# as14120_x31_usb.net
KiCad netlist of a schematic drawn in Altium Designer
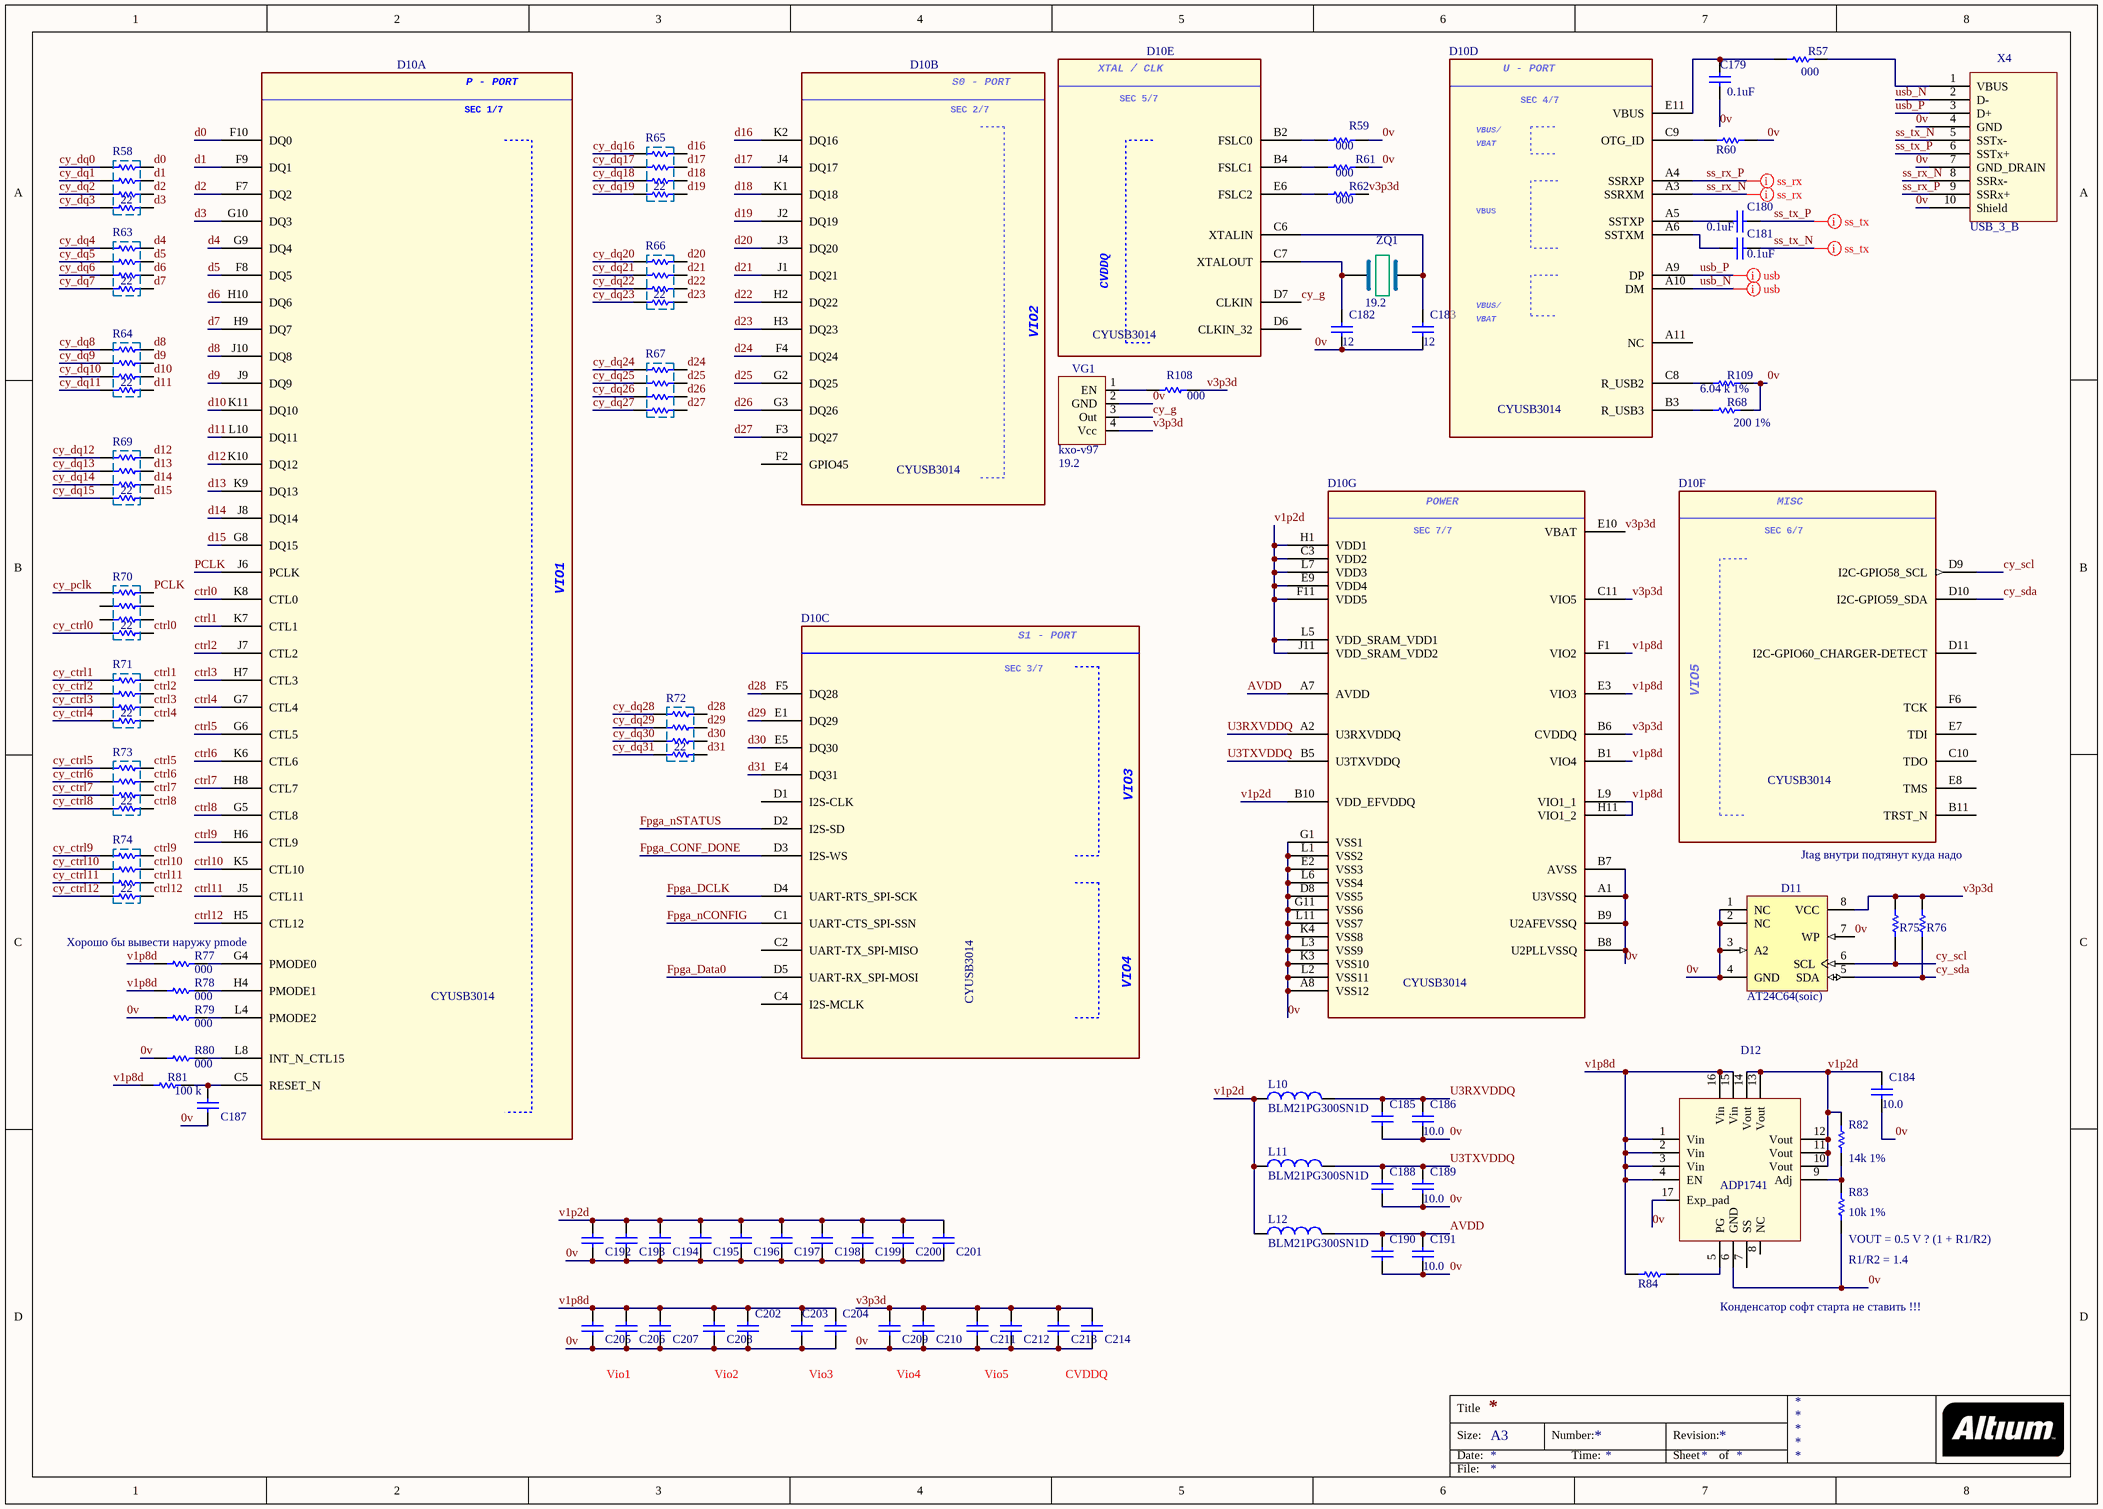
[diagram p0: as14120_x31_usb.SchDoc]

(export (version "E")
  (design (tool "Eeschema 10.0.6"))
  (components
    (comp (ref "C179")
      (value "0.1uF")
      (footprint "CAPC0402(1005)60_M")
      (description "CAP 1uF 10V ±20% 0402 (1005 Metric) Thickness 0.6mm SMD")
      (fields (field (name "TOLERANCE") "±20%") (field (name "Comment") "CAP 1uF 10V 0402(1005)"))
      (libsource (lib "as14120") (part "CAP_0402"))
    )
    (comp (ref "C180")
      (value "0.1uF")
      (footprint "CAPC0402(1005)60_M")
      (description "CAP 1uF 10V ±20% 0402 (1005 Metric) Thickness 0.6mm SMD")
      (fields (field (name "TOLERANCE") "±20%") (field (name "Comment") "CAP 1uF 10V 0402(1005)"))
      (libsource (lib "as14120") (part "CAP_0402"))
    )
    (comp (ref "C181")
      (value "0.1uF")
      (footprint "CAPC0402(1005)60_M")
      (description "CAP 1uF 10V ±20% 0402 (1005 Metric) Thickness 0.6mm SMD")
      (fields (field (name "TOLERANCE") "±20%") (field (name "Comment") "CAP 1uF 10V 0402(1005)"))
      (libsource (lib "as14120") (part "CAP_0402"))
    )
    (comp (ref "C182")
      (value "12")
      (footprint "CAPC0805(2012)100_N")
      (fields (field (name "Comment") "CAP_0805"))
      (libsource (lib "as14120") (part "CAP_0805"))
    )
    (comp (ref "C183")
      (value "12")
      (footprint "CAPC0805(2012)100_N")
      (fields (field (name "Comment") "CAP_0805"))
      (libsource (lib "as14120") (part "CAP_0805"))
    )
    (comp (ref "C184")
      (value "10.0")
      (footprint "CAPC0805(2012)100_N")
      (fields (field (name "Comment") "CAP_0805"))
      (libsource (lib "as14120") (part "CAP_0805"))
    )
    (comp (ref "C185")
      (value "CAP 1uF 10V 0402(1005)")
      (footprint "CAPC0402(1005)60_M")
      (description "CAP 1uF 10V ±20% 0402 (1005 Metric) Thickness 0.6mm SMD")
      (fields (field (name "TOLERANCE") "±20%"))
      (libsource (lib "as14120") (part "CAP_0402"))
    )
    (comp (ref "C186")
      (value "10.0")
      (footprint "CAPC0805(2012)100_N")
      (fields (field (name "Comment") "CAP_0805"))
      (libsource (lib "as14120") (part "CAP_0805"))
    )
    (comp (ref "C187")
      (value "CAP 1uF 10V 0402(1005)")
      (footprint "CAPC0402(1005)60_M")
      (description "CAP 1uF 10V ±20% 0402 (1005 Metric) Thickness 0.6mm SMD")
      (fields (field (name "TOLERANCE") "±20%"))
      (libsource (lib "as14120") (part "CAP_0402"))
    )
    (comp (ref "C188")
      (value "CAP 1uF 10V 0402(1005)")
      (footprint "CAPC0402(1005)60_M")
      (description "CAP 1uF 10V ±20% 0402 (1005 Metric) Thickness 0.6mm SMD")
      (fields (field (name "TOLERANCE") "±20%"))
      (libsource (lib "as14120") (part "CAP_0402"))
    )
    (comp (ref "C189")
      (value "10.0")
      (footprint "CAPC0805(2012)100_N")
      (fields (field (name "Comment") "CAP_0805"))
      (libsource (lib "as14120") (part "CAP_0805"))
    )
    (comp (ref "C190")
      (value "CAP 1uF 10V 0402(1005)")
      (footprint "CAPC0402(1005)60_M")
      (description "CAP 1uF 10V ±20% 0402 (1005 Metric) Thickness 0.6mm SMD")
      (fields (field (name "TOLERANCE") "±20%"))
      (libsource (lib "as14120") (part "CAP_0402"))
    )
    (comp (ref "C191")
      (value "10.0")
      (footprint "CAPC0805(2012)100_N")
      (fields (field (name "Comment") "CAP_0805"))
      (libsource (lib "as14120") (part "CAP_0805"))
    )
    (comp (ref "C192")
      (value "CAP 1uF 10V 0402(1005)")
      (footprint "CAPC0402(1005)60_M")
      (description "CAP 1uF 10V ±20% 0402 (1005 Metric) Thickness 0.6mm SMD")
      (fields (field (name "TOLERANCE") "±20%"))
      (libsource (lib "as14120") (part "CAP_0402"))
    )
    (comp (ref "C193")
      (value "CAP 1uF 10V 0402(1005)")
      (footprint "CAPC0402(1005)60_M")
      (description "CAP 1uF 10V ±20% 0402 (1005 Metric) Thickness 0.6mm SMD")
      (fields (field (name "TOLERANCE") "±20%"))
      (libsource (lib "as14120") (part "CAP_0402"))
    )
    (comp (ref "C194")
      (value "CAP 1uF 10V 0402(1005)")
      (footprint "CAPC0402(1005)60_M")
      (description "CAP 1uF 10V ±20% 0402 (1005 Metric) Thickness 0.6mm SMD")
      (fields (field (name "TOLERANCE") "±20%"))
      (libsource (lib "as14120") (part "CAP_0402"))
    )
    (comp (ref "C195")
      (value "CAP 1uF 10V 0402(1005)")
      (footprint "CAPC0402(1005)60_M")
      (description "CAP 1uF 10V ±20% 0402 (1005 Metric) Thickness 0.6mm SMD")
      (fields (field (name "TOLERANCE") "±20%"))
      (libsource (lib "as14120") (part "CAP_0402"))
    )
    (comp (ref "C196")
      (value "CAP 1uF 10V 0402(1005)")
      (footprint "CAPC0402(1005)60_M")
      (description "CAP 1uF 10V ±20% 0402 (1005 Metric) Thickness 0.6mm SMD")
      (fields (field (name "TOLERANCE") "±20%"))
      (libsource (lib "as14120") (part "CAP_0402"))
    )
    (comp (ref "C197")
      (value "CAP 1uF 10V 0402(1005)")
      (footprint "CAPC0402(1005)60_M")
      (description "CAP 1uF 10V ±20% 0402 (1005 Metric) Thickness 0.6mm SMD")
      (fields (field (name "TOLERANCE") "±20%"))
      (libsource (lib "as14120") (part "CAP_0402"))
    )
    (comp (ref "C198")
      (value "CAP 1uF 10V 0402(1005)")
      (footprint "CAPC0402(1005)60_M")
      (description "CAP 1uF 10V ±20% 0402 (1005 Metric) Thickness 0.6mm SMD")
      (fields (field (name "TOLERANCE") "±20%"))
      (libsource (lib "as14120") (part "CAP_0402"))
    )
    (comp (ref "C199")
      (value "CAP 1uF 10V 0402(1005)")
      (footprint "CAPC0402(1005)60_M")
      (description "CAP 1uF 10V ±20% 0402 (1005 Metric) Thickness 0.6mm SMD")
      (fields (field (name "TOLERANCE") "±20%"))
      (libsource (lib "as14120") (part "CAP_0402"))
    )
    (comp (ref "C200")
      (value "CAP 1uF 10V 0402(1005)")
      (footprint "CAPC0402(1005)60_M")
      (description "CAP 1uF 10V ±20% 0402 (1005 Metric) Thickness 0.6mm SMD")
      (fields (field (name "TOLERANCE") "±20%"))
      (libsource (lib "as14120") (part "CAP_0402"))
    )
    (comp (ref "C201")
      (value "CAP 1uF 10V 0402(1005)")
      (footprint "CAPC0402(1005)60_M")
      (description "CAP 1uF 10V ±20% 0402 (1005 Metric) Thickness 0.6mm SMD")
      (fields (field (name "TOLERANCE") "±20%"))
      (libsource (lib "as14120") (part "CAP_0402"))
    )
    (comp (ref "C202")
      (value "CAP 1uF 10V 0402(1005)")
      (footprint "CAPC0402(1005)60_M")
      (description "CAP 1uF 10V ±20% 0402 (1005 Metric) Thickness 0.6mm SMD")
      (fields (field (name "TOLERANCE") "±20%"))
      (libsource (lib "as14120") (part "CAP_0402"))
    )
    (comp (ref "C203")
      (value "CAP 1uF 10V 0402(1005)")
      (footprint "CAPC0402(1005)60_M")
      (description "CAP 1uF 10V ±20% 0402 (1005 Metric) Thickness 0.6mm SMD")
      (fields (field (name "TOLERANCE") "±20%"))
      (libsource (lib "as14120") (part "CAP_0402"))
    )
    (comp (ref "C204")
      (value "CAP 1uF 10V 0402(1005)")
      (footprint "CAPC0402(1005)60_M")
      (description "CAP 1uF 10V ±20% 0402 (1005 Metric) Thickness 0.6mm SMD")
      (fields (field (name "TOLERANCE") "±20%"))
      (libsource (lib "as14120") (part "CAP_0402"))
    )
    (comp (ref "C205")
      (value "CAP 1uF 10V 0402(1005)")
      (footprint "CAPC0402(1005)60_M")
      (description "CAP 1uF 10V ±20% 0402 (1005 Metric) Thickness 0.6mm SMD")
      (fields (field (name "TOLERANCE") "±20%"))
      (libsource (lib "as14120") (part "CAP_0402"))
    )
    (comp (ref "C206")
      (value "CAP 1uF 10V 0402(1005)")
      (footprint "CAPC0402(1005)60_M")
      (description "CAP 1uF 10V ±20% 0402 (1005 Metric) Thickness 0.6mm SMD")
      (fields (field (name "TOLERANCE") "±20%"))
      (libsource (lib "as14120") (part "CAP_0402"))
    )
    (comp (ref "C207")
      (value "CAP 1uF 10V 0402(1005)")
      (footprint "CAPC0402(1005)60_M")
      (description "CAP 1uF 10V ±20% 0402 (1005 Metric) Thickness 0.6mm SMD")
      (fields (field (name "TOLERANCE") "±20%"))
      (libsource (lib "as14120") (part "CAP_0402"))
    )
    (comp (ref "C208")
      (value "CAP 1uF 10V 0402(1005)")
      (footprint "CAPC0402(1005)60_M")
      (description "CAP 1uF 10V ±20% 0402 (1005 Metric) Thickness 0.6mm SMD")
      (fields (field (name "TOLERANCE") "±20%"))
      (libsource (lib "as14120") (part "CAP_0402"))
    )
    (comp (ref "C209")
      (value "CAP 1uF 10V 0402(1005)")
      (footprint "CAPC0402(1005)60_M")
      (description "CAP 1uF 10V ±20% 0402 (1005 Metric) Thickness 0.6mm SMD")
      (fields (field (name "TOLERANCE") "±20%"))
      (libsource (lib "as14120") (part "CAP_0402"))
    )
    (comp (ref "C210")
      (value "CAP 1uF 10V 0402(1005)")
      (footprint "CAPC0402(1005)60_M")
      (description "CAP 1uF 10V ±20% 0402 (1005 Metric) Thickness 0.6mm SMD")
      (fields (field (name "TOLERANCE") "±20%"))
      (libsource (lib "as14120") (part "CAP_0402"))
    )
    (comp (ref "C211")
      (value "CAP 1uF 10V 0402(1005)")
      (footprint "CAPC0402(1005)60_M")
      (description "CAP 1uF 10V ±20% 0402 (1005 Metric) Thickness 0.6mm SMD")
      (fields (field (name "TOLERANCE") "±20%"))
      (libsource (lib "as14120") (part "CAP_0402"))
    )
    (comp (ref "C212")
      (value "CAP 1uF 10V 0402(1005)")
      (footprint "CAPC0402(1005)60_M")
      (description "CAP 1uF 10V ±20% 0402 (1005 Metric) Thickness 0.6mm SMD")
      (fields (field (name "TOLERANCE") "±20%"))
      (libsource (lib "as14120") (part "CAP_0402"))
    )
    (comp (ref "C213")
      (value "CAP 1uF 10V 0402(1005)")
      (footprint "CAPC0402(1005)60_M")
      (description "CAP 1uF 10V ±20% 0402 (1005 Metric) Thickness 0.6mm SMD")
      (fields (field (name "TOLERANCE") "±20%"))
      (libsource (lib "as14120") (part "CAP_0402"))
    )
    (comp (ref "C214")
      (value "CAP 1uF 10V 0402(1005)")
      (footprint "CAPC0402(1005)60_M")
      (description "CAP 1uF 10V ±20% 0402 (1005 Metric) Thickness 0.6mm SMD")
      (fields (field (name "TOLERANCE") "±20%"))
      (libsource (lib "as14120") (part "CAP_0402"))
    )
    (comp (ref "D10")
      (value "CYUSB3014")
      (footprint "BGA121C80P11X11")
      (libsource (lib "") (part "CYUSB3014-BZXC_1"))
    )
    (comp (ref "D11")
      (value "AT24C64(soic)")
      (footprint "8S1_N")
      (libsource (lib "Atmel Serial EEPROM") (part "AT24C08BN-SP25-T"))
    )
    (comp (ref "D12") (value "ADP1741") (footprint "CP-16-4_N") (libsource (lib "as14120") (part "ADP1741")))
    (comp (ref "L10")
      (value "BLM21PG300SN1D")
      (footprint "CAPC0805(2012)100_N")
      (libsource (lib "as14120") (part "Ferrite_beat"))
    )
    (comp (ref "L11")
      (value "BLM21PG300SN1D")
      (footprint "CAPC0805(2012)100_N")
      (libsource (lib "as14120") (part "Ferrite_beat"))
    )
    (comp (ref "L12")
      (value "BLM21PG300SN1D")
      (footprint "CAPC0805(2012)100_N")
      (libsource (lib "as14120") (part "Ferrite_beat"))
    )
    (comp (ref "R57")
      (value "000")
      (footprint "RESC0805(2012)_L")
      (description "1K 0.125W 1% 0805 (2012 Metric)  SMD")
      (fields (field (name "TOLERANCE") "1 %") (field (name "POWER") "0.125 W"))
      (libsource (lib "as14120") (part "RES_0805"))
    )
    (comp (ref "R58") (value "22") (footprint "CAY16") (libsource (lib "as14120") (part "cay16-J4")))
    (comp (ref "R59")
      (value "000")
      (footprint "RESC0603(1608)_L")
      (description "1K 0.1W 5% 0603 (1608 Metric)  SMD")
      (fields (field (name "TOLERANCE") "5 %") (field (name "POWER") "0.1 W"))
      (libsource (lib "as14120") (part "RES_0603"))
    )
    (comp (ref "R60")
      (value "???")
      (footprint "RESC0603(1608)_L")
      (description "1K 0.1W 5% 0603 (1608 Metric)  SMD")
      (fields (field (name "TOLERANCE") "5 %") (field (name "POWER") "0.1 W"))
      (libsource (lib "as14120") (part "RES_0603"))
    )
    (comp (ref "R61")
      (value "000")
      (footprint "RESC0603(1608)_L")
      (description "1K 0.1W 5% 0603 (1608 Metric)  SMD")
      (fields (field (name "TOLERANCE") "5 %") (field (name "POWER") "0.1 W"))
      (libsource (lib "as14120") (part "RES_0603"))
    )
    (comp (ref "R62")
      (value "000")
      (footprint "RESC0603(1608)_L")
      (description "1K 0.1W 5% 0603 (1608 Metric)  SMD")
      (fields (field (name "TOLERANCE") "5 %") (field (name "POWER") "0.1 W"))
      (libsource (lib "as14120") (part "RES_0603"))
    )
    (comp (ref "R63") (value "22") (footprint "CAY16") (libsource (lib "as14120") (part "cay16-J4")))
    (comp (ref "R64") (value "22") (footprint "CAY16") (libsource (lib "as14120") (part "cay16-J4")))
    (comp (ref "R65") (value "22") (footprint "CAY16") (libsource (lib "as14120") (part "cay16-J4")))
    (comp (ref "R66") (value "22") (footprint "CAY16") (libsource (lib "as14120") (part "cay16-J4")))
    (comp (ref "R67") (value "~") (footprint "CAY16") (libsource (lib "as14120") (part "cay16-J4")))
    (comp (ref "R68")
      (value "200 1%")
      (footprint "RESC0805(2012)_L")
      (description "1K 0.125W 1% 0805 (2012 Metric)  SMD")
      (fields (field (name "TOLERANCE") "1 %") (field (name "POWER") "0.125 W"))
      (libsource (lib "as14120") (part "RES_0805"))
    )
    (comp (ref "R69") (value "22") (footprint "CAY16") (libsource (lib "as14120") (part "cay16-J4")))
    (comp (ref "R70") (value "22") (footprint "CAY16") (libsource (lib "as14120") (part "cay16-J4")))
    (comp (ref "R71") (value "22") (footprint "CAY16") (libsource (lib "as14120") (part "cay16-J4")))
    (comp (ref "R72") (value "22") (footprint "CAY16") (libsource (lib "as14120") (part "cay16-J4")))
    (comp (ref "R73") (value "22") (footprint "CAY16") (libsource (lib "as14120") (part "cay16-J4")))
    (comp (ref "R74") (value "22") (footprint "CAY16") (libsource (lib "as14120") (part "cay16-J4")))
    (comp (ref "R75")
      (value "1K 5% 0603(1608)")
      (footprint "RESC0603(1608)_L")
      (description "1K 0.1W 5% 0603 (1608 Metric)  SMD")
      (fields (field (name "TOLERANCE") "5 %") (field (name "POWER") "0.1 W"))
      (libsource (lib "as14120") (part "RES_0603"))
    )
    (comp (ref "R76")
      (value "1K 5% 0603(1608)")
      (footprint "RESC0603(1608)_L")
      (description "1K 0.1W 5% 0603 (1608 Metric)  SMD")
      (fields (field (name "TOLERANCE") "5 %") (field (name "POWER") "0.1 W"))
      (libsource (lib "as14120") (part "RES_0603"))
    )
    (comp (ref "R77")
      (value "000")
      (footprint "RESC0603(1608)_L")
      (description "1K 0.1W 5% 0603 (1608 Metric)  SMD")
      (fields (field (name "TOLERANCE") "5 %") (field (name "POWER") "0.1 W"))
      (libsource (lib "as14120") (part "RES_0603"))
    )
    (comp (ref "R78")
      (value "000")
      (footprint "RESC0603(1608)_L")
      (description "1K 0.1W 5% 0603 (1608 Metric)  SMD")
      (fields (field (name "TOLERANCE") "5 %") (field (name "POWER") "0.1 W"))
      (libsource (lib "as14120") (part "RES_0603"))
    )
    (comp (ref "R79")
      (value "000")
      (footprint "RESC0603(1608)_L")
      (description "1K 0.1W 5% 0603 (1608 Metric)  SMD")
      (fields (field (name "TOLERANCE") "5 %") (field (name "POWER") "0.1 W"))
      (libsource (lib "as14120") (part "RES_0603"))
    )
    (comp (ref "R80")
      (value "000")
      (footprint "RESC0603(1608)_L")
      (description "1K 0.1W 5% 0603 (1608 Metric)  SMD")
      (fields (field (name "TOLERANCE") "5 %") (field (name "POWER") "0.1 W"))
      (libsource (lib "as14120") (part "RES_0603"))
    )
    (comp (ref "R81")
      (value "100 k")
      (footprint "RESC0603(1608)_L")
      (description "1K 0.1W 5% 0603 (1608 Metric)  SMD")
      (fields (field (name "TOLERANCE") "5 %") (field (name "POWER") "0.1 W"))
      (libsource (lib "as14120") (part "RES_0603"))
    )
    (comp (ref "R82")
      (value "14k 1%")
      (footprint "RESC0805(2012)_L")
      (description "1K 0.125W 1% 0805 (2012 Metric)  SMD")
      (fields (field (name "TOLERANCE") "1 %") (field (name "POWER") "0.125 W"))
      (libsource (lib "as14120") (part "RES_0805"))
    )
    (comp (ref "R83")
      (value "10k 1%")
      (footprint "RESC0805(2012)_L")
      (description "1K 0.125W 1% 0805 (2012 Metric)  SMD")
      (fields (field (name "TOLERANCE") "1 %") (field (name "POWER") "0.125 W"))
      (libsource (lib "as14120") (part "RES_0805"))
    )
    (comp (ref "R84")
      (value "1K 5% 0603(1608)")
      (footprint "RESC0603(1608)_L")
      (description "1K 0.1W 5% 0603 (1608 Metric)  SMD")
      (fields (field (name "TOLERANCE") "5 %") (field (name "POWER") "0.1 W"))
      (libsource (lib "as14120") (part "RES_0603"))
    )
    (comp (ref "R108")
      (value "000")
      (footprint "RESC0603(1608)_L")
      (description "1K 0.1W 5% 0603 (1608 Metric)  SMD")
      (fields (field (name "TOLERANCE") "5 %") (field (name "POWER") "0.1 W"))
      (libsource (lib "as14120") (part "RES_0603"))
    )
    (comp (ref "R109")
      (value "6.04 k 1%")
      (footprint "RESC0805(2012)_L")
      (description "1K 0.125W 1% 0805 (2012 Metric)  SMD")
      (fields (field (name "TOLERANCE") "1 %") (field (name "POWER") "0.125 W"))
      (libsource (lib "as14120") (part "RES_0805"))
    )
    (comp (ref "VG1")
      (value "kxo-v97")
      (footprint "kxo-v97")
      (fields (field (name "ALTIUM_VALUE") "19.2"))
      (libsource (lib "as14120") (part "kxo-v97"))
    )
    (comp (ref "X4") (value "USB_3_B") (footprint "USB3_B") (libsource (lib "as14120") (part "USB_3_B")))
    (comp (ref "ZQ1")
      (value "19.2")
      (footprint "BCY-W2/E4.7")
      (fields (field (name "Comment") "Resonator"))
      (libsource (lib "as14120") (part "Resonator"))
    )
  )
  (nets
    (net (code "1") (name "/0v") (class "Default")
      (node (ref "C179") (pin "2") (pinfunction "2_2") (pintype "passive"))
      (node (ref "C182") (pin "1") (pinfunction "1_1") (pintype "passive"))
      (node (ref "C183") (pin "1") (pinfunction "1_1") (pintype "passive"))
      (node (ref "C184") (pin "1") (pinfunction "1_1") (pintype "passive"))
      (node (ref "C185") (pin "1") (pinfunction "1_1") (pintype "passive"))
      (node (ref "C186") (pin "1") (pinfunction "1_1") (pintype "passive"))
      (node (ref "C187") (pin "1") (pinfunction "1_1") (pintype "passive"))
      (node (ref "C188") (pin "1") (pinfunction "1_1") (pintype "passive"))
      (node (ref "C189") (pin "1") (pinfunction "1_1") (pintype "passive"))
      (node (ref "C190") (pin "1") (pinfunction "1_1") (pintype "passive"))
      (node (ref "C191") (pin "1") (pinfunction "1_1") (pintype "passive"))
      (node (ref "C192") (pin "1") (pinfunction "1_1") (pintype "passive"))
      (node (ref "C193") (pin "1") (pinfunction "1_1") (pintype "passive"))
      (node (ref "C194") (pin "1") (pinfunction "1_1") (pintype "passive"))
      (node (ref "C195") (pin "1") (pinfunction "1_1") (pintype "passive"))
      (node (ref "C196") (pin "1") (pinfunction "1_1") (pintype "passive"))
      (node (ref "C197") (pin "1") (pinfunction "1_1") (pintype "passive"))
      (node (ref "C198") (pin "1") (pinfunction "1_1") (pintype "passive"))
      (node (ref "C199") (pin "1") (pinfunction "1_1") (pintype "passive"))
      (node (ref "C200") (pin "1") (pinfunction "1_1") (pintype "passive"))
      (node (ref "C201") (pin "1") (pinfunction "1_1") (pintype "passive"))
      (node (ref "C202") (pin "1") (pinfunction "1_1") (pintype "passive"))
      (node (ref "C203") (pin "1") (pinfunction "1_1") (pintype "passive"))
      (node (ref "C204") (pin "1") (pinfunction "1_1") (pintype "passive"))
      (node (ref "C205") (pin "1") (pinfunction "1_1") (pintype "passive"))
      (node (ref "C206") (pin "1") (pinfunction "1_1") (pintype "passive"))
      (node (ref "C207") (pin "1") (pinfunction "1_1") (pintype "passive"))
      (node (ref "C208") (pin "1") (pinfunction "1_1") (pintype "passive"))
      (node (ref "C209") (pin "1") (pinfunction "1_1") (pintype "passive"))
      (node (ref "C210") (pin "1") (pinfunction "1_1") (pintype "passive"))
      (node (ref "C211") (pin "1") (pinfunction "1_1") (pintype "passive"))
      (node (ref "C212") (pin "1") (pinfunction "1_1") (pintype "passive"))
      (node (ref "C213") (pin "1") (pinfunction "1_1") (pintype "passive"))
      (node (ref "C214") (pin "1") (pinfunction "1_1") (pintype "passive"))
      (node (ref "D10") (pin "A1") (pinfunction "U3VSSQ_A1") (pintype "passive"))
      (node (ref "D10") (pin "A8") (pinfunction "VSS12_A8") (pintype "passive"))
      (node (ref "D10") (pin "B7") (pinfunction "AVSS_B7") (pintype "passive"))
      (node (ref "D10") (pin "B8") (pinfunction "U2PLLVSSQ_B8") (pintype "passive"))
      (node (ref "D10") (pin "B9") (pinfunction "U2AFEVSSQ_B9") (pintype "passive"))
      (node (ref "D10") (pin "D8") (pinfunction "VSS5_D8") (pintype "passive"))
      (node (ref "D10") (pin "E2") (pinfunction "VSS3_E2") (pintype "passive"))
      (node (ref "D10") (pin "G1") (pinfunction "VSS1_G1") (pintype "passive"))
      (node (ref "D10") (pin "G11") (pinfunction "VSS6_G11") (pintype "passive"))
      (node (ref "D10") (pin "K3") (pinfunction "VSS10_K3") (pintype "passive"))
      (node (ref "D10") (pin "K4") (pinfunction "VSS8_K4") (pintype "passive"))
      (node (ref "D10") (pin "L1") (pinfunction "VSS2_L1") (pintype "passive"))
      (node (ref "D10") (pin "L11") (pinfunction "VSS7_L11") (pintype "passive"))
      (node (ref "D10") (pin "L2") (pinfunction "VSS11_L2") (pintype "passive"))
      (node (ref "D10") (pin "L3") (pinfunction "VSS9_L3") (pintype "passive"))
      (node (ref "D10") (pin "L6") (pinfunction "VSS4_L6") (pintype "passive"))
      (node (ref "D11") (pin "1") (pinfunction "NC_1") (pintype "passive"))
      (node (ref "D11") (pin "2") (pinfunction "NC_2") (pintype "passive"))
      (node (ref "D11") (pin "3") (pinfunction "A2_3") (pintype "input"))
      (node (ref "D11") (pin "4") (pinfunction "GND_4") (pintype "power_in"))
      (node (ref "D11") (pin "7") (pinfunction "WP_7") (pintype "input"))
      (node (ref "D12") (pin "17") (pinfunction "Exp_pad_17") (pintype "passive"))
      (node (ref "D12") (pin "6") (pinfunction "GND_6") (pintype "passive"))
      (node (ref "R109") (pin "2") (pinfunction "2_2") (pintype "passive"))
      (node (ref "R59") (pin "1") (pinfunction "1_1") (pintype "passive"))
      (node (ref "R60") (pin "2") (pinfunction "2_2") (pintype "passive"))
      (node (ref "R61") (pin "1") (pinfunction "1_1") (pintype "passive"))
      (node (ref "R68") (pin "2") (pinfunction "2_2") (pintype "passive"))
      (node (ref "R79") (pin "2") (pinfunction "2_2") (pintype "passive"))
      (node (ref "R80") (pin "2") (pinfunction "2_2") (pintype "passive"))
      (node (ref "R83") (pin "1") (pinfunction "1_1") (pintype "passive"))
      (node (ref "VG1") (pin "2") (pinfunction "GND_2") (pintype "passive"))
      (node (ref "X4") (pin "10") (pinfunction "Shield_10") (pintype "passive"))
      (node (ref "X4") (pin "4") (pinfunction "GND_4") (pintype "passive"))
      (node (ref "X4") (pin "7") (pinfunction "GND_DRAIN_7") (pintype "passive"))
    )
    (net (code "2") (name "/AVDD") (class "Default")
      (node (ref "C190") (pin "2") (pinfunction "2_2") (pintype "passive"))
      (node (ref "C191") (pin "2") (pinfunction "2_2") (pintype "passive"))
      (node (ref "D10") (pin "A7") (pinfunction "AVDD_A7") (pintype "passive"))
      (node (ref "L12") (pin "2") (pinfunction "2_2") (pintype "passive"))
    )
    (net (code "3") (name "/Fpga_CONF_DONE") (class "Default")
      (node (ref "D10") (pin "D3") (pinfunction "I2S-WS_D3") (pintype "passive"))
    )
    (net (code "4") (name "/Fpga_DCLK") (class "Default")
      (node (ref "D10") (pin "D4") (pinfunction "UART-RTS_SPI-SCK_D4") (pintype "passive"))
    )
    (net (code "5") (name "/Fpga_Data0") (class "Default")
      (node (ref "D10") (pin "D5") (pinfunction "UART-RX_SPI-MOSI_D5") (pintype "passive"))
    )
    (net (code "6") (name "/Fpga_nCONFIG") (class "Default")
      (node (ref "D10") (pin "C1") (pinfunction "UART-CTS_SPI-SSN_C1") (pintype "passive"))
    )
    (net (code "7") (name "/Fpga_nSTATUS") (class "Default")
      (node (ref "D10") (pin "D2") (pinfunction "I2S-SD_D2") (pintype "passive"))
    )
    (net (code "8") (name "/PCLK") (class "Default")
      (node (ref "D10") (pin "J6") (pinfunction "PCLK_J6") (pintype "passive"))
      (node (ref "R70") (pin "8") (pinfunction "8_8") (pintype "passive"))
    )
    (net (code "9") (name "/U3RXVDDQ") (class "Default")
      (node (ref "C185") (pin "2") (pinfunction "2_2") (pintype "passive"))
      (node (ref "C186") (pin "2") (pinfunction "2_2") (pintype "passive"))
      (node (ref "D10") (pin "A2") (pinfunction "U3RXVDDQ_A2") (pintype "passive"))
      (node (ref "L10") (pin "2") (pinfunction "2_2") (pintype "passive"))
    )
    (net (code "10") (name "/U3TXVDDQ") (class "Default")
      (node (ref "C188") (pin "2") (pinfunction "2_2") (pintype "passive"))
      (node (ref "C189") (pin "2") (pinfunction "2_2") (pintype "passive"))
      (node (ref "D10") (pin "B5") (pinfunction "U3TXVDDQ_B5") (pintype "passive"))
      (node (ref "L11") (pin "2") (pinfunction "2_2") (pintype "passive"))
    )
    (net (code "11") (name "/ctrl0") (class "Default")
      (node (ref "D10") (pin "K8") (pinfunction "CTL0_K8") (pintype "passive"))
      (node (ref "R70") (pin "5") (pinfunction "5_5") (pintype "passive"))
    )
    (net (code "12") (name "/ctrl1") (class "Default")
      (node (ref "D10") (pin "K7") (pinfunction "CTL1_K7") (pintype "passive"))
      (node (ref "R71") (pin "8") (pinfunction "8_8") (pintype "passive"))
    )
    (net (code "13") (name "/ctrl2") (class "Default")
      (node (ref "D10") (pin "J7") (pinfunction "CTL2_J7") (pintype "passive"))
      (node (ref "R71") (pin "7") (pinfunction "7_7") (pintype "passive"))
    )
    (net (code "14") (name "/ctrl3") (class "Default")
      (node (ref "D10") (pin "H7") (pinfunction "CTL3_H7") (pintype "passive"))
      (node (ref "R71") (pin "6") (pinfunction "6_6") (pintype "passive"))
    )
    (net (code "15") (name "/ctrl4") (class "Default")
      (node (ref "D10") (pin "G7") (pinfunction "CTL4_G7") (pintype "passive"))
      (node (ref "R71") (pin "5") (pinfunction "5_5") (pintype "passive"))
    )
    (net (code "16") (name "/ctrl5") (class "Default")
      (node (ref "D10") (pin "G6") (pinfunction "CTL5_G6") (pintype "passive"))
      (node (ref "R73") (pin "8") (pinfunction "8_8") (pintype "passive"))
    )
    (net (code "17") (name "/ctrl6") (class "Default")
      (node (ref "D10") (pin "K6") (pinfunction "CTL6_K6") (pintype "passive"))
      (node (ref "R73") (pin "7") (pinfunction "7_7") (pintype "passive"))
    )
    (net (code "18") (name "/ctrl7") (class "Default")
      (node (ref "D10") (pin "H8") (pinfunction "CTL7_H8") (pintype "passive"))
      (node (ref "R73") (pin "6") (pinfunction "6_6") (pintype "passive"))
    )
    (net (code "19") (name "/ctrl8") (class "Default")
      (node (ref "D10") (pin "G5") (pinfunction "CTL8_G5") (pintype "passive"))
      (node (ref "R73") (pin "5") (pinfunction "5_5") (pintype "passive"))
    )
    (net (code "20") (name "/ctrl9") (class "Default")
      (node (ref "D10") (pin "H6") (pinfunction "CTL9_H6") (pintype "passive"))
      (node (ref "R74") (pin "8") (pinfunction "8_8") (pintype "passive"))
    )
    (net (code "21") (name "/ctrl10") (class "Default")
      (node (ref "D10") (pin "K5") (pinfunction "CTL10_K5") (pintype "passive"))
      (node (ref "R74") (pin "7") (pinfunction "7_7") (pintype "passive"))
    )
    (net (code "22") (name "/ctrl11") (class "Default")
      (node (ref "D10") (pin "J5") (pinfunction "CTL11_J5") (pintype "passive"))
      (node (ref "R74") (pin "6") (pinfunction "6_6") (pintype "passive"))
    )
    (net (code "23") (name "/ctrl12") (class "Default")
      (node (ref "D10") (pin "H5") (pinfunction "CTL12_H5") (pintype "passive"))
      (node (ref "R74") (pin "5") (pinfunction "5_5") (pintype "passive"))
    )
    (net (code "24") (name "/cy_ctrl0") (class "Default")
      (node (ref "R70") (pin "4") (pinfunction "4_4") (pintype "passive"))
    )
    (net (code "25") (name "/cy_ctrl1") (class "Default")
      (node (ref "R71") (pin "1") (pinfunction "1_1") (pintype "passive"))
    )
    (net (code "26") (name "/cy_ctrl2") (class "Default")
      (node (ref "R71") (pin "2") (pinfunction "2_2") (pintype "passive"))
    )
    (net (code "27") (name "/cy_ctrl3") (class "Default")
      (node (ref "R71") (pin "3") (pinfunction "3_3") (pintype "passive"))
    )
    (net (code "28") (name "/cy_ctrl4") (class "Default")
      (node (ref "R71") (pin "4") (pinfunction "4_4") (pintype "passive"))
    )
    (net (code "29") (name "/cy_ctrl5") (class "Default")
      (node (ref "R73") (pin "1") (pinfunction "1_1") (pintype "passive"))
    )
    (net (code "30") (name "/cy_ctrl6") (class "Default")
      (node (ref "R73") (pin "2") (pinfunction "2_2") (pintype "passive"))
    )
    (net (code "31") (name "/cy_ctrl7") (class "Default")
      (node (ref "R73") (pin "3") (pinfunction "3_3") (pintype "passive"))
    )
    (net (code "32") (name "/cy_ctrl8") (class "Default")
      (node (ref "R73") (pin "4") (pinfunction "4_4") (pintype "passive"))
    )
    (net (code "33") (name "/cy_ctrl9") (class "Default")
      (node (ref "R74") (pin "1") (pinfunction "1_1") (pintype "passive"))
    )
    (net (code "34") (name "/cy_ctrl10") (class "Default")
      (node (ref "R74") (pin "2") (pinfunction "2_2") (pintype "passive"))
    )
    (net (code "35") (name "/cy_ctrl11") (class "Default")
      (node (ref "R74") (pin "3") (pinfunction "3_3") (pintype "passive"))
    )
    (net (code "36") (name "/cy_ctrl12") (class "Default")
      (node (ref "R74") (pin "4") (pinfunction "4_4") (pintype "passive"))
    )
    (net (code "37") (name "/cy_dq0") (class "Default")
      (node (ref "R58") (pin "1") (pinfunction "1_1") (pintype "passive"))
    )
    (net (code "38") (name "/cy_dq1") (class "Default")
      (node (ref "R58") (pin "2") (pinfunction "2_2") (pintype "passive"))
    )
    (net (code "39") (name "/cy_dq2") (class "Default")
      (node (ref "R58") (pin "3") (pinfunction "3_3") (pintype "passive"))
    )
    (net (code "40") (name "/cy_dq3") (class "Default")
      (node (ref "R58") (pin "4") (pinfunction "4_4") (pintype "passive"))
    )
    (net (code "41") (name "/cy_dq4") (class "Default")
      (node (ref "R63") (pin "1") (pinfunction "1_1") (pintype "passive"))
    )
    (net (code "42") (name "/cy_dq5") (class "Default")
      (node (ref "R63") (pin "2") (pinfunction "2_2") (pintype "passive"))
    )
    (net (code "43") (name "/cy_dq6") (class "Default")
      (node (ref "R63") (pin "3") (pinfunction "3_3") (pintype "passive"))
    )
    (net (code "44") (name "/cy_dq7") (class "Default")
      (node (ref "R63") (pin "4") (pinfunction "4_4") (pintype "passive"))
    )
    (net (code "45") (name "/cy_dq8") (class "Default")
      (node (ref "R64") (pin "1") (pinfunction "1_1") (pintype "passive"))
    )
    (net (code "46") (name "/cy_dq9") (class "Default")
      (node (ref "R64") (pin "2") (pinfunction "2_2") (pintype "passive"))
    )
    (net (code "47") (name "/cy_dq10") (class "Default")
      (node (ref "R64") (pin "3") (pinfunction "3_3") (pintype "passive"))
    )
    (net (code "48") (name "/cy_dq11") (class "Default")
      (node (ref "R64") (pin "4") (pinfunction "4_4") (pintype "passive"))
    )
    (net (code "49") (name "/cy_dq12") (class "Default")
      (node (ref "R69") (pin "1") (pinfunction "1_1") (pintype "passive"))
    )
    (net (code "50") (name "/cy_dq13") (class "Default")
      (node (ref "R69") (pin "2") (pinfunction "2_2") (pintype "passive"))
    )
    (net (code "51") (name "/cy_dq14") (class "Default")
      (node (ref "R69") (pin "3") (pinfunction "3_3") (pintype "passive"))
    )
    (net (code "52") (name "/cy_dq15") (class "Default")
      (node (ref "R69") (pin "4") (pinfunction "4_4") (pintype "passive"))
    )
    (net (code "53") (name "/cy_dq16") (class "Default")
      (node (ref "R65") (pin "1") (pinfunction "1_1") (pintype "passive"))
    )
    (net (code "54") (name "/cy_dq17") (class "Default")
      (node (ref "R65") (pin "2") (pinfunction "2_2") (pintype "passive"))
    )
    (net (code "55") (name "/cy_dq18") (class "Default")
      (node (ref "R65") (pin "3") (pinfunction "3_3") (pintype "passive"))
    )
    (net (code "56") (name "/cy_dq19") (class "Default")
      (node (ref "R65") (pin "4") (pinfunction "4_4") (pintype "passive"))
    )
    (net (code "57") (name "/cy_dq20") (class "Default")
      (node (ref "R66") (pin "1") (pinfunction "1_1") (pintype "passive"))
    )
    (net (code "58") (name "/cy_dq21") (class "Default")
      (node (ref "R66") (pin "2") (pinfunction "2_2") (pintype "passive"))
    )
    (net (code "59") (name "/cy_dq22") (class "Default")
      (node (ref "R66") (pin "3") (pinfunction "3_3") (pintype "passive"))
    )
    (net (code "60") (name "/cy_dq23") (class "Default")
      (node (ref "R66") (pin "4") (pinfunction "4_4") (pintype "passive"))
    )
    (net (code "61") (name "/cy_dq24") (class "Default")
      (node (ref "R67") (pin "1") (pinfunction "1_1") (pintype "passive"))
    )
    (net (code "62") (name "/cy_dq25") (class "Default")
      (node (ref "R67") (pin "2") (pinfunction "2_2") (pintype "passive"))
    )
    (net (code "63") (name "/cy_dq26") (class "Default")
      (node (ref "R67") (pin "3") (pinfunction "3_3") (pintype "passive"))
    )
    (net (code "64") (name "/cy_dq27") (class "Default")
      (node (ref "R67") (pin "4") (pinfunction "4_4") (pintype "passive"))
    )
    (net (code "65") (name "/cy_dq28") (class "Default")
      (node (ref "R72") (pin "1") (pinfunction "1_1") (pintype "passive"))
    )
    (net (code "66") (name "/cy_dq29") (class "Default")
      (node (ref "R72") (pin "2") (pinfunction "2_2") (pintype "passive"))
    )
    (net (code "67") (name "/cy_dq30") (class "Default")
      (node (ref "R72") (pin "3") (pinfunction "3_3") (pintype "passive"))
    )
    (net (code "68") (name "/cy_dq31") (class "Default")
      (node (ref "R72") (pin "4") (pinfunction "4_4") (pintype "passive"))
    )
    (net (code "69") (name "/cy_g") (class "Default")
      (node (ref "D10") (pin "D7") (pinfunction "CLKIN_D7") (pintype "passive"))
      (node (ref "VG1") (pin "3") (pinfunction "Out_3") (pintype "passive"))
    )
    (net (code "70") (name "/cy_pclk") (class "Default")
      (node (ref "R70") (pin "1") (pinfunction "1_1") (pintype "passive"))
    )
    (net (code "71") (name "/cy_scl") (class "Default")
      (node (ref "D10") (pin "D9") (pinfunction "I2C-GPIO58_SCL_D9") (pintype "output"))
      (node (ref "D11") (pin "6") (pinfunction "SCL_6") (pintype "input"))
      (node (ref "R75") (pin "1") (pinfunction "1_1") (pintype "passive"))
    )
    (net (code "72") (name "/cy_sda") (class "Default")
      (node (ref "D10") (pin "D10") (pinfunction "I2C-GPIO59_SDA_D10") (pintype "passive"))
      (node (ref "D11") (pin "5") (pinfunction "SDA_5") (pintype "bidirectional"))
      (node (ref "R76") (pin "1") (pinfunction "1_1") (pintype "passive"))
    )
    (net (code "73") (name "/d0") (class "Default")
      (node (ref "D10") (pin "F10") (pinfunction "DQ0_F10") (pintype "passive"))
      (node (ref "R58") (pin "8") (pinfunction "8_8") (pintype "passive"))
    )
    (net (code "74") (name "/d1") (class "Default")
      (node (ref "D10") (pin "F9") (pinfunction "DQ1_F9") (pintype "passive"))
      (node (ref "R58") (pin "7") (pinfunction "7_7") (pintype "passive"))
    )
    (net (code "75") (name "/d2") (class "Default")
      (node (ref "D10") (pin "F7") (pinfunction "DQ2_F7") (pintype "passive"))
      (node (ref "R58") (pin "6") (pinfunction "6_6") (pintype "passive"))
    )
    (net (code "76") (name "/d3") (class "Default")
      (node (ref "D10") (pin "G10") (pinfunction "DQ3_G10") (pintype "passive"))
      (node (ref "R58") (pin "5") (pinfunction "5_5") (pintype "passive"))
    )
    (net (code "77") (name "/d4") (class "Default")
      (node (ref "D10") (pin "G9") (pinfunction "DQ4_G9") (pintype "passive"))
      (node (ref "R63") (pin "8") (pinfunction "8_8") (pintype "passive"))
    )
    (net (code "78") (name "/d5") (class "Default")
      (node (ref "D10") (pin "F8") (pinfunction "DQ5_F8") (pintype "passive"))
      (node (ref "R63") (pin "7") (pinfunction "7_7") (pintype "passive"))
    )
    (net (code "79") (name "/d6") (class "Default")
      (node (ref "D10") (pin "H10") (pinfunction "DQ6_H10") (pintype "passive"))
      (node (ref "R63") (pin "6") (pinfunction "6_6") (pintype "passive"))
    )
    (net (code "80") (name "/d7") (class "Default")
      (node (ref "D10") (pin "H9") (pinfunction "DQ7_H9") (pintype "passive"))
      (node (ref "R63") (pin "5") (pinfunction "5_5") (pintype "passive"))
    )
    (net (code "81") (name "/d8") (class "Default")
      (node (ref "D10") (pin "J10") (pinfunction "DQ8_J10") (pintype "passive"))
      (node (ref "R64") (pin "8") (pinfunction "8_8") (pintype "passive"))
    )
    (net (code "82") (name "/d9") (class "Default")
      (node (ref "D10") (pin "J9") (pinfunction "DQ9_J9") (pintype "passive"))
      (node (ref "R64") (pin "7") (pinfunction "7_7") (pintype "passive"))
    )
    (net (code "83") (name "/d10") (class "Default")
      (node (ref "D10") (pin "K11") (pinfunction "DQ10_K11") (pintype "passive"))
      (node (ref "R64") (pin "6") (pinfunction "6_6") (pintype "passive"))
    )
    (net (code "84") (name "/d11") (class "Default")
      (node (ref "D10") (pin "L10") (pinfunction "DQ11_L10") (pintype "passive"))
      (node (ref "R64") (pin "5") (pinfunction "5_5") (pintype "passive"))
    )
    (net (code "85") (name "/d12") (class "Default")
      (node (ref "D10") (pin "K10") (pinfunction "DQ12_K10") (pintype "passive"))
      (node (ref "R69") (pin "8") (pinfunction "8_8") (pintype "passive"))
    )
    (net (code "86") (name "/d13") (class "Default")
      (node (ref "D10") (pin "K9") (pinfunction "DQ13_K9") (pintype "passive"))
      (node (ref "R69") (pin "7") (pinfunction "7_7") (pintype "passive"))
    )
    (net (code "87") (name "/d14") (class "Default")
      (node (ref "D10") (pin "J8") (pinfunction "DQ14_J8") (pintype "passive"))
      (node (ref "R69") (pin "6") (pinfunction "6_6") (pintype "passive"))
    )
    (net (code "88") (name "/d15") (class "Default")
      (node (ref "D10") (pin "G8") (pinfunction "DQ15_G8") (pintype "passive"))
      (node (ref "R69") (pin "5") (pinfunction "5_5") (pintype "passive"))
    )
    (net (code "89") (name "/d16") (class "Default")
      (node (ref "D10") (pin "K2") (pinfunction "DQ16_K2") (pintype "passive"))
      (node (ref "R65") (pin "8") (pinfunction "8_8") (pintype "passive"))
    )
    (net (code "90") (name "/d17") (class "Default")
      (node (ref "D10") (pin "J4") (pinfunction "DQ17_J4") (pintype "passive"))
      (node (ref "R65") (pin "7") (pinfunction "7_7") (pintype "passive"))
    )
    (net (code "91") (name "/d18") (class "Default")
      (node (ref "D10") (pin "K1") (pinfunction "DQ18_K1") (pintype "passive"))
      (node (ref "R65") (pin "6") (pinfunction "6_6") (pintype "passive"))
    )
    (net (code "92") (name "/d19") (class "Default")
      (node (ref "D10") (pin "J2") (pinfunction "DQ19_J2") (pintype "passive"))
      (node (ref "R65") (pin "5") (pinfunction "5_5") (pintype "passive"))
    )
    (net (code "93") (name "/d20") (class "Default")
      (node (ref "D10") (pin "J3") (pinfunction "DQ20_J3") (pintype "passive"))
      (node (ref "R66") (pin "8") (pinfunction "8_8") (pintype "passive"))
    )
    (net (code "94") (name "/d21") (class "Default")
      (node (ref "D10") (pin "J1") (pinfunction "DQ21_J1") (pintype "passive"))
      (node (ref "R66") (pin "7") (pinfunction "7_7") (pintype "passive"))
    )
    (net (code "95") (name "/d22") (class "Default")
      (node (ref "D10") (pin "H2") (pinfunction "DQ22_H2") (pintype "passive"))
      (node (ref "R66") (pin "6") (pinfunction "6_6") (pintype "passive"))
    )
    (net (code "96") (name "/d23") (class "Default")
      (node (ref "D10") (pin "H3") (pinfunction "DQ23_H3") (pintype "passive"))
      (node (ref "R66") (pin "5") (pinfunction "5_5") (pintype "passive"))
    )
    (net (code "97") (name "/d24") (class "Default")
      (node (ref "D10") (pin "F4") (pinfunction "DQ24_F4") (pintype "passive"))
      (node (ref "R67") (pin "8") (pinfunction "8_8") (pintype "passive"))
    )
    (net (code "98") (name "/d25") (class "Default")
      (node (ref "D10") (pin "G2") (pinfunction "DQ25_G2") (pintype "passive"))
      (node (ref "R67") (pin "7") (pinfunction "7_7") (pintype "passive"))
    )
    (net (code "99") (name "/d26") (class "Default")
      (node (ref "D10") (pin "G3") (pinfunction "DQ26_G3") (pintype "passive"))
      (node (ref "R67") (pin "6") (pinfunction "6_6") (pintype "passive"))
    )
    (net (code "100") (name "/d27") (class "Default")
      (node (ref "D10") (pin "F3") (pinfunction "DQ27_F3") (pintype "passive"))
      (node (ref "R67") (pin "5") (pinfunction "5_5") (pintype "passive"))
    )
    (net (code "101") (name "/d28") (class "Default")
      (node (ref "D10") (pin "F5") (pinfunction "DQ28_F5") (pintype "passive"))
      (node (ref "R72") (pin "8") (pinfunction "8_8") (pintype "passive"))
    )
    (net (code "102") (name "/d29") (class "Default")
      (node (ref "D10") (pin "E1") (pinfunction "DQ29_E1") (pintype "passive"))
      (node (ref "R72") (pin "7") (pinfunction "7_7") (pintype "passive"))
    )
    (net (code "103") (name "/d30") (class "Default")
      (node (ref "D10") (pin "E5") (pinfunction "DQ30_E5") (pintype "passive"))
      (node (ref "R72") (pin "6") (pinfunction "6_6") (pintype "passive"))
    )
    (net (code "104") (name "/d31") (class "Default")
      (node (ref "D10") (pin "E4") (pinfunction "DQ31_E4") (pintype "passive"))
      (node (ref "R72") (pin "5") (pinfunction "5_5") (pintype "passive"))
    )
    (net (code "105") (name "/ss_rx_N") (class "Default")
      (node (ref "D10") (pin "A3") (pinfunction "SSRXM_A3") (pintype "passive"))
      (node (ref "X4") (pin "8") (pinfunction "SSRx-_8") (pintype "passive"))
    )
    (net (code "106") (name "/ss_rx_P") (class "Default")
      (node (ref "D10") (pin "A4") (pinfunction "SSRXP_A4") (pintype "passive"))
      (node (ref "X4") (pin "9") (pinfunction "SSRx+_9") (pintype "passive"))
    )
    (net (code "107") (name "/ss_tx_N") (class "Default")
      (node (ref "C181") (pin "1") (pinfunction "1_1") (pintype "passive"))
      (node (ref "X4") (pin "5") (pinfunction "SSTx-_5") (pintype "passive"))
    )
    (net (code "108") (name "/ss_tx_P") (class "Default")
      (node (ref "C180") (pin "1") (pinfunction "1_1") (pintype "passive"))
      (node (ref "X4") (pin "6") (pinfunction "SSTx+_6") (pintype "passive"))
    )
    (net (code "109") (name "/usb_N") (class "Default")
      (node (ref "D10") (pin "A10") (pinfunction "DM_A10") (pintype "passive"))
      (node (ref "X4") (pin "2") (pinfunction "D-_2") (pintype "passive"))
    )
    (net (code "110") (name "/usb_P") (class "Default")
      (node (ref "D10") (pin "A9") (pinfunction "DP_A9") (pintype "passive"))
      (node (ref "X4") (pin "3") (pinfunction "D+_3") (pintype "passive"))
    )
    (net (code "111") (name "/v1p2d") (class "Default")
      (node (ref "C184") (pin "2") (pinfunction "2_2") (pintype "passive"))
      (node (ref "C192") (pin "2") (pinfunction "2_2") (pintype "passive"))
      (node (ref "C193") (pin "2") (pinfunction "2_2") (pintype "passive"))
      (node (ref "C194") (pin "2") (pinfunction "2_2") (pintype "passive"))
      (node (ref "C195") (pin "2") (pinfunction "2_2") (pintype "passive"))
      (node (ref "C196") (pin "2") (pinfunction "2_2") (pintype "passive"))
      (node (ref "C197") (pin "2") (pinfunction "2_2") (pintype "passive"))
      (node (ref "C198") (pin "2") (pinfunction "2_2") (pintype "passive"))
      (node (ref "C199") (pin "2") (pinfunction "2_2") (pintype "passive"))
      (node (ref "C200") (pin "2") (pinfunction "2_2") (pintype "passive"))
      (node (ref "C201") (pin "2") (pinfunction "2_2") (pintype "passive"))
      (node (ref "D10") (pin "B10") (pinfunction "VDD_EFVDDQ_B10") (pintype "passive"))
      (node (ref "D10") (pin "C3") (pinfunction "VDD2_C3") (pintype "passive"))
      (node (ref "D10") (pin "E9") (pinfunction "VDD4_E9") (pintype "passive"))
      (node (ref "D10") (pin "F11") (pinfunction "VDD5_F11") (pintype "passive"))
      (node (ref "D10") (pin "H1") (pinfunction "VDD1_H1") (pintype "passive"))
      (node (ref "D10") (pin "J11") (pinfunction "VDD_SRAM_VDD2_J11") (pintype "passive"))
      (node (ref "D10") (pin "L5") (pinfunction "VDD_SRAM_VDD1_L5") (pintype "passive"))
      (node (ref "D10") (pin "L7") (pinfunction "VDD3_L7") (pintype "passive"))
      (node (ref "D12") (pin "10") (pinfunction "Vout_10") (pintype "passive"))
      (node (ref "D12") (pin "11") (pinfunction "Vout_11") (pintype "passive"))
      (node (ref "D12") (pin "12") (pinfunction "Vout_12") (pintype "passive"))
      (node (ref "D12") (pin "13") (pinfunction "Vout_13") (pintype "passive"))
      (node (ref "D12") (pin "14") (pinfunction "Vout_14") (pintype "passive"))
      (node (ref "L10") (pin "1") (pinfunction "1_1") (pintype "passive"))
      (node (ref "L11") (pin "1") (pinfunction "1_1") (pintype "passive"))
      (node (ref "L12") (pin "1") (pinfunction "1_1") (pintype "passive"))
      (node (ref "R82") (pin "2") (pinfunction "2_2") (pintype "passive"))
    )
    (net (code "112") (name "/v1p8d") (class "Default")
      (node (ref "C202") (pin "2") (pinfunction "2_2") (pintype "passive"))
      (node (ref "C203") (pin "2") (pinfunction "2_2") (pintype "passive"))
      (node (ref "C204") (pin "2") (pinfunction "2_2") (pintype "passive"))
      (node (ref "C205") (pin "2") (pinfunction "2_2") (pintype "passive"))
      (node (ref "C206") (pin "2") (pinfunction "2_2") (pintype "passive"))
      (node (ref "C207") (pin "2") (pinfunction "2_2") (pintype "passive"))
      (node (ref "C208") (pin "2") (pinfunction "2_2") (pintype "passive"))
      (node (ref "D10") (pin "B1") (pinfunction "VIO4_B1") (pintype "passive"))
      (node (ref "D10") (pin "E3") (pinfunction "VIO3_E3") (pintype "passive"))
      (node (ref "D10") (pin "F1") (pinfunction "VIO2_F1") (pintype "passive"))
      (node (ref "D10") (pin "H11") (pinfunction "VIO1_2_H11") (pintype "passive"))
      (node (ref "D10") (pin "L9") (pinfunction "VIO1_1_L9") (pintype "passive"))
      (node (ref "D12") (pin "1") (pinfunction "Vin_1") (pintype "passive"))
      (node (ref "D12") (pin "15") (pinfunction "Vin_15") (pintype "passive"))
      (node (ref "D12") (pin "16") (pinfunction "Vin_16") (pintype "passive"))
      (node (ref "D12") (pin "2") (pinfunction "Vin_2") (pintype "passive"))
      (node (ref "D12") (pin "3") (pinfunction "Vin_3") (pintype "passive"))
      (node (ref "D12") (pin "4") (pinfunction "EN_4") (pintype "passive"))
      (node (ref "R77") (pin "2") (pinfunction "2_2") (pintype "passive"))
      (node (ref "R78") (pin "2") (pinfunction "2_2") (pintype "passive"))
      (node (ref "R81") (pin "2") (pinfunction "2_2") (pintype "passive"))
      (node (ref "R84") (pin "2") (pinfunction "2_2") (pintype "passive"))
    )
    (net (code "113") (name "/v3p3d") (class "Default")
      (node (ref "C209") (pin "2") (pinfunction "2_2") (pintype "passive"))
      (node (ref "C210") (pin "2") (pinfunction "2_2") (pintype "passive"))
      (node (ref "C211") (pin "2") (pinfunction "2_2") (pintype "passive"))
      (node (ref "C212") (pin "2") (pinfunction "2_2") (pintype "passive"))
      (node (ref "C213") (pin "2") (pinfunction "2_2") (pintype "passive"))
      (node (ref "C214") (pin "2") (pinfunction "2_2") (pintype "passive"))
      (node (ref "D10") (pin "B6") (pinfunction "CVDDQ_B6") (pintype "passive"))
      (node (ref "D10") (pin "C11") (pinfunction "VIO5_C11") (pintype "passive"))
      (node (ref "D10") (pin "E10") (pinfunction "VBAT_E10") (pintype "passive"))
      (node (ref "D11") (pin "8") (pinfunction "VCC_8") (pintype "power_in"))
      (node (ref "R108") (pin "1") (pinfunction "1_1") (pintype "passive"))
      (node (ref "R62") (pin "1") (pinfunction "1_1") (pintype "passive"))
      (node (ref "R75") (pin "2") (pinfunction "2_2") (pintype "passive"))
      (node (ref "R76") (pin "2") (pinfunction "2_2") (pintype "passive"))
      (node (ref "VG1") (pin "4") (pinfunction "Vcc_4") (pintype "passive"))
    )
    (net (code "114") (name "Net-(D10A-INT_N_CTL15)") (class "Default")
      (node (ref "D10") (pin "L8") (pinfunction "INT_N_CTL15_L8") (pintype "passive"))
      (node (ref "R80") (pin "1") (pinfunction "1_1") (pintype "passive"))
    )
    (net (code "115") (name "Net-(D10A-PMODE0)") (class "Default")
      (node (ref "D10") (pin "G4") (pinfunction "PMODE0_G4") (pintype "passive"))
      (node (ref "R77") (pin "1") (pinfunction "1_1") (pintype "passive"))
    )
    (net (code "116") (name "Net-(D10A-PMODE1)") (class "Default")
      (node (ref "D10") (pin "H4") (pinfunction "PMODE1_H4") (pintype "passive"))
      (node (ref "R78") (pin "1") (pinfunction "1_1") (pintype "passive"))
    )
    (net (code "117") (name "Net-(D10A-PMODE2)") (class "Default")
      (node (ref "D10") (pin "L4") (pinfunction "PMODE2_L4") (pintype "passive"))
      (node (ref "R79") (pin "1") (pinfunction "1_1") (pintype "passive"))
    )
    (net (code "118") (name "Net-(D10A-RESET_N)") (class "Default")
      (node (ref "C187") (pin "2") (pinfunction "2_2") (pintype "passive"))
      (node (ref "D10") (pin "C5") (pinfunction "RESET_N_C5") (pintype "passive"))
      (node (ref "R81") (pin "1") (pinfunction "1_1") (pintype "passive"))
    )
    (net (code "119") (name "Net-(D10D-OTG_ID)") (class "Default")
      (node (ref "D10") (pin "C9") (pinfunction "OTG_ID_C9") (pintype "passive"))
      (node (ref "R60") (pin "1") (pinfunction "1_1") (pintype "passive"))
    )
    (net (code "120") (name "Net-(D10D-R_USB2)") (class "Default")
      (node (ref "D10") (pin "C8") (pinfunction "R_USB2_C8") (pintype "passive"))
      (node (ref "R109") (pin "1") (pinfunction "1_1") (pintype "passive"))
    )
    (net (code "121") (name "Net-(D10D-R_USB3)") (class "Default")
      (node (ref "D10") (pin "B3") (pinfunction "R_USB3_B3") (pintype "passive"))
      (node (ref "R68") (pin "1") (pinfunction "1_1") (pintype "passive"))
    )
    (net (code "122") (name "Net-(D10D-SSTXM)") (class "Default")
      (node (ref "C181") (pin "2") (pinfunction "2_2") (pintype "passive"))
      (node (ref "D10") (pin "A6") (pinfunction "SSTXM_A6") (pintype "passive"))
    )
    (net (code "123") (name "Net-(D10D-SSTXP)") (class "Default")
      (node (ref "C180") (pin "2") (pinfunction "2_2") (pintype "passive"))
      (node (ref "D10") (pin "A5") (pinfunction "SSTXP_A5") (pintype "passive"))
    )
    (net (code "124") (name "Net-(D10D-VBUS)") (class "Default")
      (node (ref "C179") (pin "1") (pinfunction "1_1") (pintype "passive"))
      (node (ref "D10") (pin "E11") (pinfunction "VBUS_E11") (pintype "passive"))
      (node (ref "R57") (pin "1") (pinfunction "1_1") (pintype "passive"))
    )
    (net (code "125") (name "Net-(D10E-FSLC0)") (class "Default")
      (node (ref "D10") (pin "B2") (pinfunction "FSLC0_B2") (pintype "passive"))
      (node (ref "R59") (pin "2") (pinfunction "2_2") (pintype "passive"))
    )
    (net (code "126") (name "Net-(D10E-FSLC1)") (class "Default")
      (node (ref "D10") (pin "B4") (pinfunction "FSLC1_B4") (pintype "passive"))
      (node (ref "R61") (pin "2") (pinfunction "2_2") (pintype "passive"))
    )
    (net (code "127") (name "Net-(D10E-FSLC2)") (class "Default")
      (node (ref "D10") (pin "E6") (pinfunction "FSLC2_E6") (pintype "passive"))
      (node (ref "R62") (pin "2") (pinfunction "2_2") (pintype "passive"))
    )
    (net (code "128") (name "Net-(D10E-XTALIN)") (class "Default")
      (node (ref "C183") (pin "2") (pinfunction "2_2") (pintype "passive"))
      (node (ref "D10") (pin "C6") (pinfunction "XTALIN_C6") (pintype "passive"))
      (node (ref "ZQ1") (pin "2") (pinfunction "2_2") (pintype "passive"))
    )
    (net (code "129") (name "Net-(D10E-XTALOUT)") (class "Default")
      (node (ref "C182") (pin "2") (pinfunction "2_2") (pintype "passive"))
      (node (ref "D10") (pin "C7") (pinfunction "XTALOUT_C7") (pintype "passive"))
      (node (ref "ZQ1") (pin "1") (pinfunction "1_1") (pintype "passive"))
    )
    (net (code "130") (name "Net-(D12-Adj)") (class "Default")
      (node (ref "D12") (pin "9") (pinfunction "Adj_9") (pintype "passive"))
      (node (ref "R82") (pin "1") (pinfunction "1_1") (pintype "passive"))
      (node (ref "R83") (pin "2") (pinfunction "2_2") (pintype "passive"))
    )
    (net (code "131") (name "Net-(D12-PG)") (class "Default")
      (node (ref "D12") (pin "5") (pinfunction "PG_5") (pintype "passive"))
      (node (ref "R84") (pin "1") (pinfunction "1_1") (pintype "passive"))
    )
    (net (code "132") (name "Net-(VG1-EN)") (class "Default")
      (node (ref "R108") (pin "2") (pinfunction "2_2") (pintype "passive"))
      (node (ref "VG1") (pin "1") (pinfunction "EN_1") (pintype "passive"))
    )
    (net (code "133") (name "Net-(X4-VBUS)") (class "Default")
      (node (ref "R57") (pin "2") (pinfunction "2_2") (pintype "passive"))
      (node (ref "X4") (pin "1") (pinfunction "VBUS_1") (pintype "passive"))
    )
    (net (code "134") (name "unconnected-(D10B-GPIO45-PadF2)") (class "Default")
      (node (ref "D10") (pin "F2") (pinfunction "GPIO45_F2") (pintype "passive"))
    )
    (net (code "135") (name "unconnected-(D10C-I2S-CLK-PadD1)") (class "Default")
      (node (ref "D10") (pin "D1") (pinfunction "I2S-CLK_D1") (pintype "passive"))
    )
    (net (code "136") (name "unconnected-(D10C-I2S-MCLK-PadC4)") (class "Default")
      (node (ref "D10") (pin "C4") (pinfunction "I2S-MCLK_C4") (pintype "passive"))
    )
    (net (code "137") (name "unconnected-(D10C-UART-TX_SPI-MISO-PadC2)") (class "Default")
      (node (ref "D10") (pin "C2") (pinfunction "UART-TX_SPI-MISO_C2") (pintype "passive"))
    )
    (net (code "138") (name "unconnected-(D10D-NC-PadA11)") (class "Default")
      (node (ref "D10") (pin "A11") (pinfunction "NC_A11") (pintype "passive"))
    )
    (net (code "139") (name "unconnected-(D10E-CLKIN_32-PadD6)") (class "Default")
      (node (ref "D10") (pin "D6") (pinfunction "CLKIN_32_D6") (pintype "passive"))
    )
    (net (code "140") (name "unconnected-(D10F-I2C-GPIO60_CHARGER-DETECT-PadD11)") (class "Default")
      (node (ref "D10") (pin "D11") (pinfunction "I2C-GPIO60_CHARGER-DETECT_D11") (pintype "passive"))
    )
    (net (code "141") (name "unconnected-(D10F-TCK-PadF6)") (class "Default")
      (node (ref "D10") (pin "F6") (pinfunction "TCK_F6") (pintype "passive"))
    )
    (net (code "142") (name "unconnected-(D10F-TDI-PadE7)") (class "Default")
      (node (ref "D10") (pin "E7") (pinfunction "TDI_E7") (pintype "passive"))
    )
    (net (code "143") (name "unconnected-(D10F-TDO-PadC10)") (class "Default")
      (node (ref "D10") (pin "C10") (pinfunction "TDO_C10") (pintype "passive"))
    )
    (net (code "144") (name "unconnected-(D10F-TMS-PadE8)") (class "Default")
      (node (ref "D10") (pin "E8") (pinfunction "TMS_E8") (pintype "passive"))
    )
    (net (code "145") (name "unconnected-(D10F-TRST_N-PadB11)") (class "Default")
      (node (ref "D10") (pin "B11") (pinfunction "TRST_N_B11") (pintype "passive"))
    )
    (net (code "146") (name "unconnected-(D12-NC-Pad8)") (class "Default")
      (node (ref "D12") (pin "8") (pinfunction "NC_8") (pintype "passive"))
    )
    (net (code "147") (name "unconnected-(D12-SS-Pad7)") (class "Default")
      (node (ref "D12") (pin "7") (pinfunction "SS_7") (pintype "passive"))
    )
    (net (code "148") (name "unconnected-(R70-Pad2)") (class "Default")
      (node (ref "R70") (pin "2") (pinfunction "2_2") (pintype "passive"))
    )
    (net (code "149") (name "unconnected-(R70-Pad3)") (class "Default")
      (node (ref "R70") (pin "3") (pinfunction "3_3") (pintype "passive"))
    )
    (net (code "150") (name "unconnected-(R70-Pad6)") (class "Default")
      (node (ref "R70") (pin "6") (pinfunction "6_6") (pintype "passive"))
    )
    (net (code "151") (name "unconnected-(R70-Pad7)") (class "Default")
      (node (ref "R70") (pin "7") (pinfunction "7_7") (pintype "passive"))
    )
  )
)
